# robot.net
KiCad netlist of a schematic drawn in EAGLE
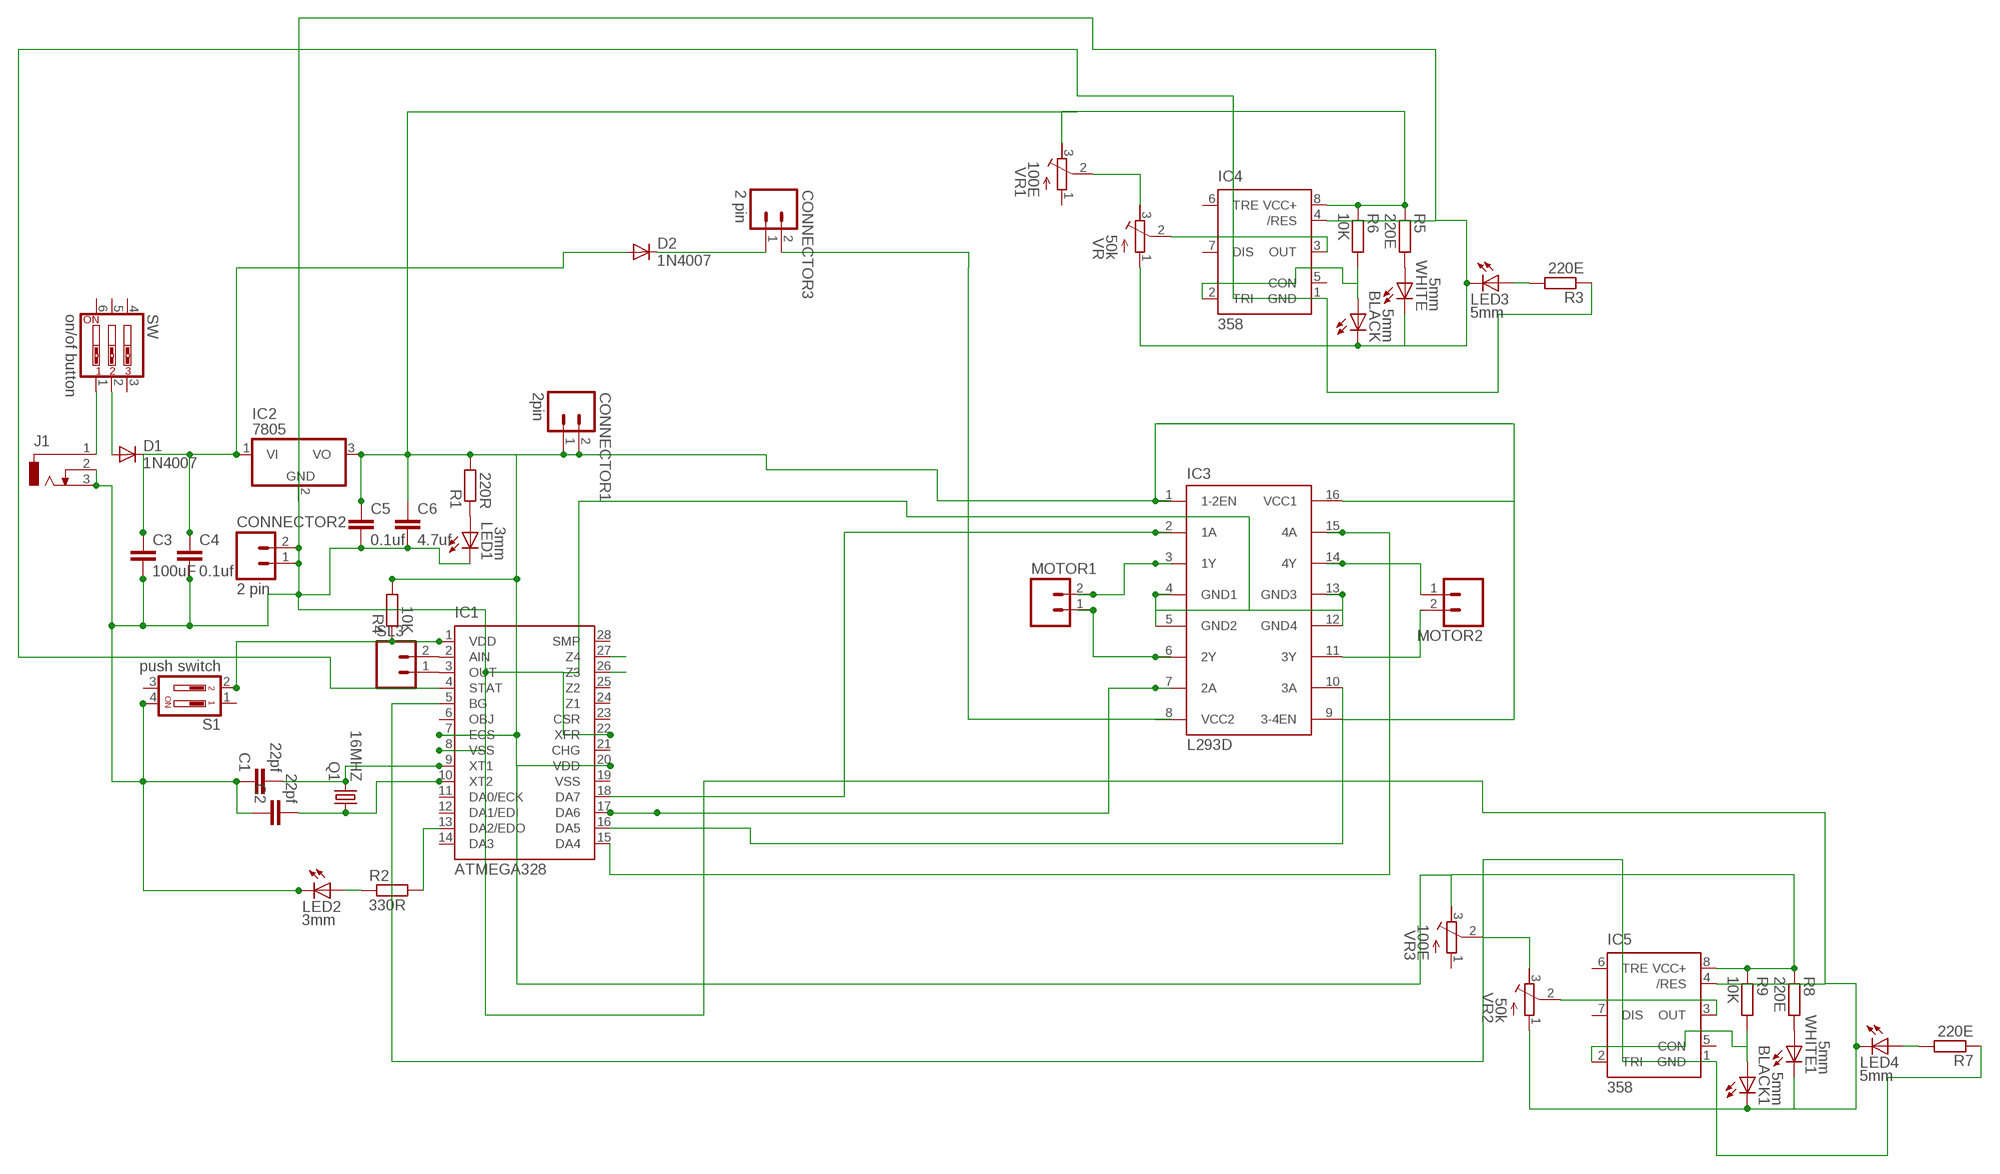
[diagram p0: schematic, sheet 1]

(export (version "E")
  (design (tool "Eeschema 10.0.6"))
  (components
    (comp (ref "BLACK")
      (value "5mm")
      (footprint "eagle-import:LED5MM")
      (libsource (lib "eagle-import") (part "LED5MM"))
    )
    (comp (ref "BLACK1")
      (value "5mm")
      (footprint "eagle-import:LED5MM")
      (libsource (lib "eagle-import") (part "LED5MM"))
    )
    (comp (ref "C1")
      (value "22pf")
      (footprint "eagle-import:C2.5-2")
      (libsource (lib "eagle-import") (part "C2.5/2"))
    )
    (comp (ref "C2")
      (value "22pf")
      (footprint "eagle-import:C2.5-2")
      (libsource (lib "eagle-import") (part "C2.5/2"))
    )
    (comp (ref "C3")
      (value "100uF")
      (footprint "eagle-import:C2.5-2")
      (libsource (lib "eagle-import") (part "C2.5/2"))
    )
    (comp (ref "C4")
      (value "0.1uf")
      (footprint "eagle-import:C2.5-2")
      (libsource (lib "eagle-import") (part "C2.5/2"))
    )
    (comp (ref "C5")
      (value "0.1uf")
      (footprint "eagle-import:C2.5-2")
      (libsource (lib "eagle-import") (part "C2.5/2"))
    )
    (comp (ref "C6")
      (value "4.7uf")
      (footprint "eagle-import:C2.5-2")
      (libsource (lib "eagle-import") (part "C2.5/2"))
    )
    (comp (ref "CONNECTOR1")
      (value "2pin")
      (footprint "eagle-import:02P")
      (fields (field (name "OC_FARNELL") "unknown") (field (name "OC_NEWARK") "unknown"))
      (libsource (lib "eagle-import") (part "M02"))
    )
    (comp (ref "CONNECTOR2")
      (value "2 pin")
      (footprint "eagle-import:02P")
      (fields (field (name "OC_FARNELL") "unknown") (field (name "OC_NEWARK") "unknown"))
      (libsource (lib "eagle-import") (part "M02"))
    )
    (comp (ref "CONNECTOR3")
      (value "2 pin")
      (footprint "eagle-import:02P")
      (fields (field (name "OC_FARNELL") "unknown") (field (name "OC_NEWARK") "unknown"))
      (libsource (lib "eagle-import") (part "M02"))
    )
    (comp (ref "D1")
      (value "1N4007")
      (footprint "eagle-import:DO41-10")
      (libsource (lib "eagle-import") (part "1N4004"))
    )
    (comp (ref "D2")
      (value "1N4007")
      (footprint "eagle-import:DO41-10")
      (libsource (lib "eagle-import") (part "1N4004"))
    )
    (comp (ref "IC1")
      (value "ATMEGA328")
      (footprint "eagle-import:DIL28-3")
      (libsource (lib "eagle-import") (part "QT9701BD"))
    )
    (comp (ref "IC2")
      (value "7805")
      (footprint "eagle-import:TO220V")
      (libsource (lib "eagle-import") (part "78TV6"))
    )
    (comp (ref "IC3")
      (value "L293D")
      (footprint "eagle-import:DIL16")
      (libsource (lib "eagle-import") (part "L293D"))
    )
    (comp (ref "IC4")
      (value "358")
      (footprint "eagle-import:DIL-08")
      (fields (field (name "MF") "Arrow Electronics") (field (name "MPN") "NE555N"))
      (libsource (lib "eagle-import") (part "NE555"))
    )
    (comp (ref "IC5")
      (value "358")
      (footprint "eagle-import:DIL-08")
      (fields (field (name "MF") "Arrow Electronics") (field (name "MPN") "NE555N"))
      (libsource (lib "eagle-import") (part "NE555"))
    )
    (comp (ref "J1")
      (value "DCJ0303")
      (footprint "eagle-import:DCJ0303")
      (libsource (lib "eagle-import") (part "DCJ0303"))
    )
    (comp (ref "LED1")
      (value "3mm")
      (footprint "eagle-import:LED3MM")
      (libsource (lib "eagle-import") (part "LED3MM"))
    )
    (comp (ref "LED2")
      (value "3mm")
      (footprint "eagle-import:LED3MM")
      (libsource (lib "eagle-import") (part "LED3MM"))
    )
    (comp (ref "LED3")
      (value "5mm")
      (footprint "eagle-import:LED5MM")
      (libsource (lib "eagle-import") (part "LED5MM"))
    )
    (comp (ref "LED4")
      (value "5mm")
      (footprint "eagle-import:LED5MM")
      (libsource (lib "eagle-import") (part "LED5MM"))
    )
    (comp (ref "MOTOR1")
      (value "M02")
      (footprint "eagle-import:02P")
      (fields (field (name "OC_FARNELL") "unknown") (field (name "OC_NEWARK") "unknown"))
      (libsource (lib "eagle-import") (part "M02"))
    )
    (comp (ref "MOTOR2")
      (value "M02")
      (footprint "eagle-import:02P")
      (libsource (lib "eagle-import") (part "M02"))
    )
    (comp (ref "Q1")
      (value "16MHZ")
      (footprint "eagle-import:HC49_S")
      (libsource (lib "eagle-import") (part "CRYSTALHC49S"))
    )
    (comp (ref "R1")
      (value "220R")
      (footprint "eagle-import:0207_10")
      (libsource (lib "eagle-import") (part "R-EU_0207/10"))
    )
    (comp (ref "R2")
      (value "330R")
      (footprint "eagle-import:0207_10")
      (libsource (lib "eagle-import") (part "R-EU_0207/10"))
    )
    (comp (ref "R3")
      (value "220E")
      (footprint "eagle-import:0204_7")
      (libsource (lib "eagle-import") (part "R-EU_0204/7"))
    )
    (comp (ref "R4")
      (value "10K")
      (footprint "eagle-import:0207_10")
      (libsource (lib "eagle-import") (part "R-EU_0207/10"))
    )
    (comp (ref "R5")
      (value "220E")
      (footprint "eagle-import:0204_7")
      (libsource (lib "eagle-import") (part "R-EU_0204/7"))
    )
    (comp (ref "R6")
      (value "10K")
      (footprint "eagle-import:0204_7")
      (libsource (lib "eagle-import") (part "R-EU_0204/7"))
    )
    (comp (ref "R7")
      (value "220E")
      (footprint "eagle-import:0204_7")
      (libsource (lib "eagle-import") (part "R-EU_0204/7"))
    )
    (comp (ref "R8")
      (value "220E")
      (footprint "eagle-import:0204_7")
      (libsource (lib "eagle-import") (part "R-EU_0204/7"))
    )
    (comp (ref "R9")
      (value "10K")
      (footprint "eagle-import:0204_7")
      (libsource (lib "eagle-import") (part "R-EU_0204/7"))
    )
    (comp (ref "S1")
      (value "push switch")
      (footprint "eagle-import:DP-02")
      (fields (field (name "MPN") "MCDP02"))
      (libsource (lib "eagle-import") (part "DP02"))
    )
    (comp (ref "SL3")
      (value "M02")
      (footprint "eagle-import:02P")
      (libsource (lib "eagle-import") (part "M02"))
    )
    (comp (ref "SW")
      (value "on/of button")
      (footprint "eagle-import:EDG-03")
      (libsource (lib "eagle-import") (part "SW_DIP-3"))
    )
    (comp (ref "VR")
      (value "50k")
      (footprint "eagle-import:RTRIM64P")
      (libsource (lib "eagle-import") (part "R-TRIMM64P"))
    )
    (comp (ref "VR1")
      (value "100E")
      (footprint "eagle-import:RTRIM64P")
      (libsource (lib "eagle-import") (part "R-TRIMM64P"))
    )
    (comp (ref "VR2")
      (value "50k")
      (footprint "eagle-import:RTRIM64P")
      (libsource (lib "eagle-import") (part "R-TRIMM64P"))
    )
    (comp (ref "VR3")
      (value "100E")
      (footprint "eagle-import:RTRIM64P")
      (libsource (lib "eagle-import") (part "R-TRIMM64P"))
    )
    (comp (ref "WHITE")
      (value "5mm")
      (footprint "eagle-import:LED5MM")
      (libsource (lib "eagle-import") (part "LED5MM"))
    )
    (comp (ref "WHITE1")
      (value "5mm")
      (footprint "eagle-import:LED5MM")
      (libsource (lib "eagle-import") (part "LED5MM"))
    )
  )
  (nets
    (net (code "1") (name "Net-(BLACK-C)") (class "Default")
      (node (ref "BLACK") (pin "K") (pinfunction "C_K") (pintype "passive"))
      (node (ref "BLACK1") (pin "K") (pinfunction "C_K") (pintype "passive"))
      (node (ref "C1") (pin "1") (pinfunction "1_1") (pintype "passive"))
      (node (ref "C2") (pin "1") (pinfunction "1_1") (pintype "passive"))
      (node (ref "C3") (pin "2") (pinfunction "2_2") (pintype "passive"))
      (node (ref "C4") (pin "2") (pinfunction "2_2") (pintype "passive"))
      (node (ref "C5") (pin "2") (pinfunction "2_2") (pintype "passive"))
      (node (ref "C6") (pin "2") (pinfunction "2_2") (pintype "passive"))
      (node (ref "CONNECTOR2") (pin "1") (pinfunction "1_1") (pintype "passive"))
      (node (ref "CONNECTOR2") (pin "2") (pinfunction "2_2") (pintype "passive"))
      (node (ref "IC1") (pin "22") (pinfunction "XFR_22") (pintype "output"))
      (node (ref "IC1") (pin "8") (pinfunction "VSS_8") (pintype "input"))
      (node (ref "IC2") (pin "2") (pinfunction "GND_2") (pintype "passive"))
      (node (ref "IC3") (pin "12") (pinfunction "GND4_12") (pintype "power_in"))
      (node (ref "IC3") (pin "13") (pinfunction "GND3_13") (pintype "power_in"))
      (node (ref "IC3") (pin "4") (pinfunction "GND1_4") (pintype "power_in"))
      (node (ref "IC3") (pin "5") (pinfunction "GND2_5") (pintype "power_in"))
      (node (ref "IC4") (pin "4") (pinfunction "/RES_4") (pintype "input"))
      (node (ref "IC5") (pin "4") (pinfunction "/RES_4") (pintype "input"))
      (node (ref "J1") (pin "2") (pinfunction "2_2") (pintype "passive"))
      (node (ref "J1") (pin "3") (pinfunction "3_3") (pintype "passive"))
      (node (ref "LED1") (pin "K") (pinfunction "C_K") (pintype "passive"))
      (node (ref "LED2") (pin "K") (pinfunction "C_K") (pintype "passive"))
      (node (ref "LED3") (pin "K") (pinfunction "C_K") (pintype "passive"))
      (node (ref "LED4") (pin "K") (pinfunction "C_K") (pintype "passive"))
      (node (ref "S1") (pin "4") (pinfunction "4_4") (pintype "passive"))
      (node (ref "VR") (pin "1") (pinfunction "E_1") (pintype "passive"))
      (node (ref "VR2") (pin "1") (pinfunction "E_1") (pintype "passive"))
      (node (ref "WHITE") (pin "K") (pinfunction "C_K") (pintype "passive"))
      (node (ref "WHITE1") (pin "K") (pinfunction "C_K") (pintype "passive"))
    )
    (net (code "2") (name "Net-(CONNECTOR3-Pad1)") (class "Default")
      (node (ref "CONNECTOR3") (pin "1") (pinfunction "1_1") (pintype "passive"))
      (node (ref "D2") (pin "C") (pinfunction "C_C") (pintype "passive"))
    )
    (net (code "3") (name "Net-(D1-PadA)") (class "Default")
      (node (ref "D1") (pin "A") (pinfunction "A_A") (pintype "passive"))
      (node (ref "SW") (pin "2") (pinfunction "2_2") (pintype "passive"))
    )
    (net (code "4") (name "Net-(IC1-AIN)") (class "Default")
      (node (ref "IC1") (pin "2") (pinfunction "AIN_2") (pintype "input"))
      (node (ref "SL3") (pin "2") (pinfunction "2_2") (pintype "passive"))
    )
    (net (code "5") (name "Net-(IC1-BG)") (class "Default")
      (node (ref "IC1") (pin "5") (pinfunction "BG_5") (pintype "input"))
      (node (ref "IC5") (pin "1") (pinfunction "GND_1") (pintype "power_in"))
      (node (ref "R7") (pin "1") (pinfunction "1_1") (pintype "passive"))
    )
    (net (code "6") (name "Net-(IC1-DA2{slash}EDO)") (class "Default")
      (node (ref "IC1") (pin "13") (pinfunction "DA2/EDO_13") (pintype "output"))
      (node (ref "R2") (pin "2") (pinfunction "2_2") (pintype "passive"))
    )
    (net (code "7") (name "Net-(IC1-DA4)") (class "Default")
      (node (ref "IC1") (pin "15") (pinfunction "DA4_15") (pintype "output"))
      (node (ref "IC3") (pin "15") (pinfunction "4A_15") (pintype "input"))
    )
    (net (code "8") (name "Net-(IC1-DA5)") (class "Default")
      (node (ref "IC1") (pin "16") (pinfunction "DA5_16") (pintype "output"))
      (node (ref "IC3") (pin "10") (pinfunction "3A_10") (pintype "input"))
    )
    (net (code "9") (name "Net-(IC1-DA6)") (class "Default")
      (node (ref "IC1") (pin "17") (pinfunction "DA6_17") (pintype "output"))
      (node (ref "IC3") (pin "7") (pinfunction "2A_7") (pintype "input"))
    )
    (net (code "10") (name "Net-(IC1-DA7)") (class "Default")
      (node (ref "IC1") (pin "18") (pinfunction "DA7_18") (pintype "output"))
      (node (ref "IC3") (pin "2") (pinfunction "1A_2") (pintype "input"))
    )
    (net (code "11") (name "Net-(IC1-ECS)") (class "Default")
      (node (ref "C5") (pin "1") (pinfunction "1_1") (pintype "passive"))
      (node (ref "C6") (pin "1") (pinfunction "1_1") (pintype "passive"))
      (node (ref "CONNECTOR1") (pin "1") (pinfunction "1_1") (pintype "passive"))
      (node (ref "CONNECTOR1") (pin "2") (pinfunction "2_2") (pintype "passive"))
      (node (ref "IC1") (pin "20") (pinfunction "VDD_20") (pintype "input"))
      (node (ref "IC1") (pin "7") (pinfunction "ECS_7") (pintype "output"))
      (node (ref "IC2") (pin "3") (pinfunction "VO_3") (pintype "passive"))
      (node (ref "IC3") (pin "1") (pinfunction "1-2EN_1") (pintype "input"))
      (node (ref "IC3") (pin "16") (pinfunction "VCC1_16") (pintype "power_in"))
      (node (ref "IC3") (pin "9") (pinfunction "3-4EN_9") (pintype "input"))
      (node (ref "IC4") (pin "8") (pinfunction "VCC+_8") (pintype "power_in"))
      (node (ref "IC5") (pin "8") (pinfunction "VCC+_8") (pintype "power_in"))
      (node (ref "R1") (pin "2") (pinfunction "2_2") (pintype "passive"))
      (node (ref "R4") (pin "2") (pinfunction "2_2") (pintype "passive"))
      (node (ref "R5") (pin "1") (pinfunction "1_1") (pintype "passive"))
      (node (ref "R6") (pin "1") (pinfunction "1_1") (pintype "passive"))
      (node (ref "R8") (pin "1") (pinfunction "1_1") (pintype "passive"))
      (node (ref "R9") (pin "1") (pinfunction "1_1") (pintype "passive"))
      (node (ref "VR1") (pin "3") (pinfunction "A_3") (pintype "passive"))
      (node (ref "VR3") (pin "3") (pinfunction "A_3") (pintype "passive"))
    )
    (net (code "12") (name "Net-(IC1-OUT)") (class "Default")
      (node (ref "IC1") (pin "3") (pinfunction "OUT_3") (pintype "output"))
      (node (ref "SL3") (pin "1") (pinfunction "1_1") (pintype "passive"))
    )
    (net (code "13") (name "Net-(IC1-STAT)") (class "Default")
      (node (ref "IC1") (pin "4") (pinfunction "STAT_4") (pintype "output"))
      (node (ref "IC4") (pin "1") (pinfunction "GND_1") (pintype "power_in"))
      (node (ref "R3") (pin "1") (pinfunction "1_1") (pintype "passive"))
    )
    (net (code "14") (name "Net-(IC1-VDD-Pad1)") (class "Default")
      (node (ref "IC1") (pin "1") (pinfunction "VDD_1") (pintype "input"))
      (node (ref "R4") (pin "1") (pinfunction "1_1") (pintype "passive"))
      (node (ref "S1") (pin "2") (pinfunction "2_2") (pintype "passive"))
    )
    (net (code "15") (name "Net-(IC1-XT1)") (class "Default")
      (node (ref "C1") (pin "2") (pinfunction "2_2") (pintype "passive"))
      (node (ref "IC1") (pin "9") (pinfunction "XT1_9") (pintype "input"))
      (node (ref "Q1") (pin "2") (pinfunction "2_2") (pintype "passive"))
    )
    (net (code "16") (name "Net-(IC1-XT2)") (class "Default")
      (node (ref "C2") (pin "2") (pinfunction "2_2") (pintype "passive"))
      (node (ref "IC1") (pin "10") (pinfunction "XT2_10") (pintype "output"))
      (node (ref "Q1") (pin "1") (pinfunction "1_1") (pintype "passive"))
    )
    (net (code "17") (name "Net-(IC2-VI)") (class "Default")
      (node (ref "C3") (pin "1") (pinfunction "1_1") (pintype "passive"))
      (node (ref "C4") (pin "1") (pinfunction "1_1") (pintype "passive"))
      (node (ref "D1") (pin "C") (pinfunction "C_C") (pintype "passive"))
      (node (ref "D2") (pin "A") (pinfunction "A_A") (pintype "passive"))
      (node (ref "IC2") (pin "1") (pinfunction "VI_1") (pintype "input"))
    )
    (net (code "18") (name "Net-(IC3-1Y)") (class "Default")
      (node (ref "IC3") (pin "3") (pinfunction "1Y_3") (pintype "output"))
      (node (ref "MOTOR1") (pin "2") (pinfunction "2_2") (pintype "passive"))
    )
    (net (code "19") (name "Net-(IC3-2Y)") (class "Default")
      (node (ref "IC3") (pin "6") (pinfunction "2Y_6") (pintype "output"))
      (node (ref "MOTOR1") (pin "1") (pinfunction "1_1") (pintype "passive"))
    )
    (net (code "20") (name "Net-(IC3-3Y)") (class "Default")
      (node (ref "IC3") (pin "11") (pinfunction "3Y_11") (pintype "output"))
      (node (ref "MOTOR2") (pin "2") (pinfunction "2_2") (pintype "passive"))
    )
    (net (code "21") (name "Net-(IC3-4Y)") (class "Default")
      (node (ref "IC3") (pin "14") (pinfunction "4Y_14") (pintype "output"))
      (node (ref "MOTOR2") (pin "1") (pinfunction "1_1") (pintype "passive"))
    )
    (net (code "22") (name "Net-(IC3-VCC2)") (class "Default")
      (node (ref "CONNECTOR3") (pin "2") (pinfunction "2_2") (pintype "passive"))
      (node (ref "IC3") (pin "8") (pinfunction "VCC2_8") (pintype "power_in"))
    )
    (net (code "23") (name "Net-(IC4-OUT)") (class "Default")
      (node (ref "IC4") (pin "3") (pinfunction "OUT_3") (pintype "output"))
      (node (ref "VR") (pin "2") (pinfunction "S_2") (pintype "passive"))
    )
    (net (code "24") (name "Net-(IC4-TRI)") (class "Default")
      (node (ref "BLACK") (pin "A") (pinfunction "A_A") (pintype "passive"))
      (node (ref "IC4") (pin "2") (pinfunction "TRI_2") (pintype "input"))
      (node (ref "R6") (pin "2") (pinfunction "2_2") (pintype "passive"))
    )
    (net (code "25") (name "Net-(IC5-OUT)") (class "Default")
      (node (ref "IC5") (pin "3") (pinfunction "OUT_3") (pintype "output"))
      (node (ref "VR2") (pin "2") (pinfunction "S_2") (pintype "passive"))
    )
    (net (code "26") (name "Net-(IC5-TRI)") (class "Default")
      (node (ref "BLACK1") (pin "A") (pinfunction "A_A") (pintype "passive"))
      (node (ref "IC5") (pin "2") (pinfunction "TRI_2") (pintype "input"))
      (node (ref "R9") (pin "2") (pinfunction "2_2") (pintype "passive"))
    )
    (net (code "27") (name "Net-(J1-Pad1)") (class "Default")
      (node (ref "J1") (pin "1") (pinfunction "1_1") (pintype "passive"))
      (node (ref "SW") (pin "1") (pinfunction "1_1") (pintype "passive"))
    )
    (net (code "28") (name "Net-(LED1-PadA)") (class "Default")
      (node (ref "LED1") (pin "A") (pinfunction "A_A") (pintype "passive"))
      (node (ref "R1") (pin "1") (pinfunction "1_1") (pintype "passive"))
    )
    (net (code "29") (name "Net-(LED2-PadA)") (class "Default")
      (node (ref "LED2") (pin "A") (pinfunction "A_A") (pintype "passive"))
      (node (ref "R2") (pin "1") (pinfunction "1_1") (pintype "passive"))
    )
    (net (code "30") (name "Net-(LED3-PadA)") (class "Default")
      (node (ref "LED3") (pin "A") (pinfunction "A_A") (pintype "passive"))
      (node (ref "R3") (pin "2") (pinfunction "2_2") (pintype "passive"))
    )
    (net (code "31") (name "Net-(LED4-PadA)") (class "Default")
      (node (ref "LED4") (pin "A") (pinfunction "A_A") (pintype "passive"))
      (node (ref "R7") (pin "2") (pinfunction "2_2") (pintype "passive"))
    )
    (net (code "32") (name "Net-(R5-Pad2)") (class "Default")
      (node (ref "R5") (pin "2") (pinfunction "2_2") (pintype "passive"))
      (node (ref "WHITE") (pin "A") (pinfunction "A_A") (pintype "passive"))
    )
    (net (code "33") (name "Net-(R8-Pad2)") (class "Default")
      (node (ref "R8") (pin "2") (pinfunction "2_2") (pintype "passive"))
      (node (ref "WHITE1") (pin "A") (pinfunction "A_A") (pintype "passive"))
    )
    (net (code "34") (name "Net-(VR-A)") (class "Default")
      (node (ref "VR") (pin "3") (pinfunction "A_3") (pintype "passive"))
      (node (ref "VR1") (pin "2") (pinfunction "S_2") (pintype "passive"))
    )
    (net (code "35") (name "Net-(VR2-A)") (class "Default")
      (node (ref "VR2") (pin "3") (pinfunction "A_3") (pintype "passive"))
      (node (ref "VR3") (pin "2") (pinfunction "S_2") (pintype "passive"))
    )
    (net (code "36") (name "unconnected-(IC1-CHG-Pad21)") (class "Default")
      (node (ref "IC1") (pin "21") (pinfunction "CHG_21") (pintype "output"))
    )
    (net (code "37") (name "unconnected-(IC1-CSR-Pad23)") (class "Default")
      (node (ref "IC1") (pin "23") (pinfunction "CSR_23") (pintype "output"))
    )
    (net (code "38") (name "unconnected-(IC1-DA0{slash}ECK-Pad11)") (class "Default")
      (node (ref "IC1") (pin "11") (pinfunction "DA0/ECK_11") (pintype "output"))
    )
    (net (code "39") (name "unconnected-(IC1-DA1{slash}EDI-Pad12)") (class "Default")
      (node (ref "IC1") (pin "12") (pinfunction "DA1/EDI_12") (pintype "output"))
    )
    (net (code "40") (name "unconnected-(IC1-DA3-Pad14)") (class "Default")
      (node (ref "IC1") (pin "14") (pinfunction "DA3_14") (pintype "output"))
    )
    (net (code "41") (name "unconnected-(IC1-OBJ-Pad6)") (class "Default")
      (node (ref "IC1") (pin "6") (pinfunction "OBJ_6") (pintype "input"))
    )
    (net (code "42") (name "unconnected-(IC1-SMP-Pad28)") (class "Default")
      (node (ref "IC1") (pin "28") (pinfunction "SMP_28") (pintype "output"))
    )
    (net (code "43") (name "unconnected-(IC1-VSS-Pad19)") (class "Default")
      (node (ref "IC1") (pin "19") (pinfunction "VSS_19") (pintype "input"))
    )
    (net (code "44") (name "unconnected-(IC1-Z1-Pad24)") (class "Default")
      (node (ref "IC1") (pin "24") (pinfunction "Z1_24") (pintype "output"))
    )
    (net (code "45") (name "unconnected-(IC1-Z2-Pad25)") (class "Default")
      (node (ref "IC1") (pin "25") (pinfunction "Z2_25") (pintype "output"))
    )
    (net (code "46") (name "unconnected-(IC1-Z3-Pad26)") (class "Default")
      (node (ref "IC1") (pin "26") (pinfunction "Z3_26") (pintype "output"))
    )
    (net (code "47") (name "unconnected-(IC1-Z4-Pad27)") (class "Default")
      (node (ref "IC1") (pin "27") (pinfunction "Z4_27") (pintype "output"))
    )
    (net (code "48") (name "unconnected-(IC4-CON-Pad5)") (class "Default")
      (node (ref "IC4") (pin "5") (pinfunction "CON_5") (pintype "input"))
    )
    (net (code "49") (name "unconnected-(IC4-DIS-Pad7)") (class "Default")
      (node (ref "IC4") (pin "7") (pinfunction "DIS_7") (pintype "input"))
    )
    (net (code "50") (name "unconnected-(IC4-TRE-Pad6)") (class "Default")
      (node (ref "IC4") (pin "6") (pinfunction "TRE_6") (pintype "input"))
    )
    (net (code "51") (name "unconnected-(IC5-CON-Pad5)") (class "Default")
      (node (ref "IC5") (pin "5") (pinfunction "CON_5") (pintype "input"))
    )
    (net (code "52") (name "unconnected-(IC5-DIS-Pad7)") (class "Default")
      (node (ref "IC5") (pin "7") (pinfunction "DIS_7") (pintype "input"))
    )
    (net (code "53") (name "unconnected-(IC5-TRE-Pad6)") (class "Default")
      (node (ref "IC5") (pin "6") (pinfunction "TRE_6") (pintype "input"))
    )
    (net (code "54") (name "unconnected-(S1-Pad1)") (class "Default")
      (node (ref "S1") (pin "1") (pinfunction "1_1") (pintype "passive"))
    )
    (net (code "55") (name "unconnected-(S1-Pad3)") (class "Default")
      (node (ref "S1") (pin "3") (pinfunction "3_3") (pintype "passive"))
    )
    (net (code "56") (name "unconnected-(SW-Pad3)") (class "Default")
      (node (ref "SW") (pin "3") (pinfunction "3_3") (pintype "passive"))
    )
    (net (code "57") (name "unconnected-(SW-Pad4)") (class "Default")
      (node (ref "SW") (pin "4") (pinfunction "4_4") (pintype "passive"))
    )
    (net (code "58") (name "unconnected-(SW-Pad5)") (class "Default")
      (node (ref "SW") (pin "5") (pinfunction "5_5") (pintype "passive"))
    )
    (net (code "59") (name "unconnected-(SW-Pad6)") (class "Default")
      (node (ref "SW") (pin "6") (pinfunction "6_6") (pintype "passive"))
    )
    (net (code "60") (name "unconnected-(VR1-E-Pad1)") (class "Default")
      (node (ref "VR1") (pin "1") (pinfunction "E_1") (pintype "passive"))
    )
    (net (code "61") (name "unconnected-(VR3-E-Pad1)") (class "Default")
      (node (ref "VR3") (pin "1") (pinfunction "E_1") (pintype "passive"))
    )
  )
)
